# Power_Supply.net
KiCad netlist of a schematic drawn in Altium Designer
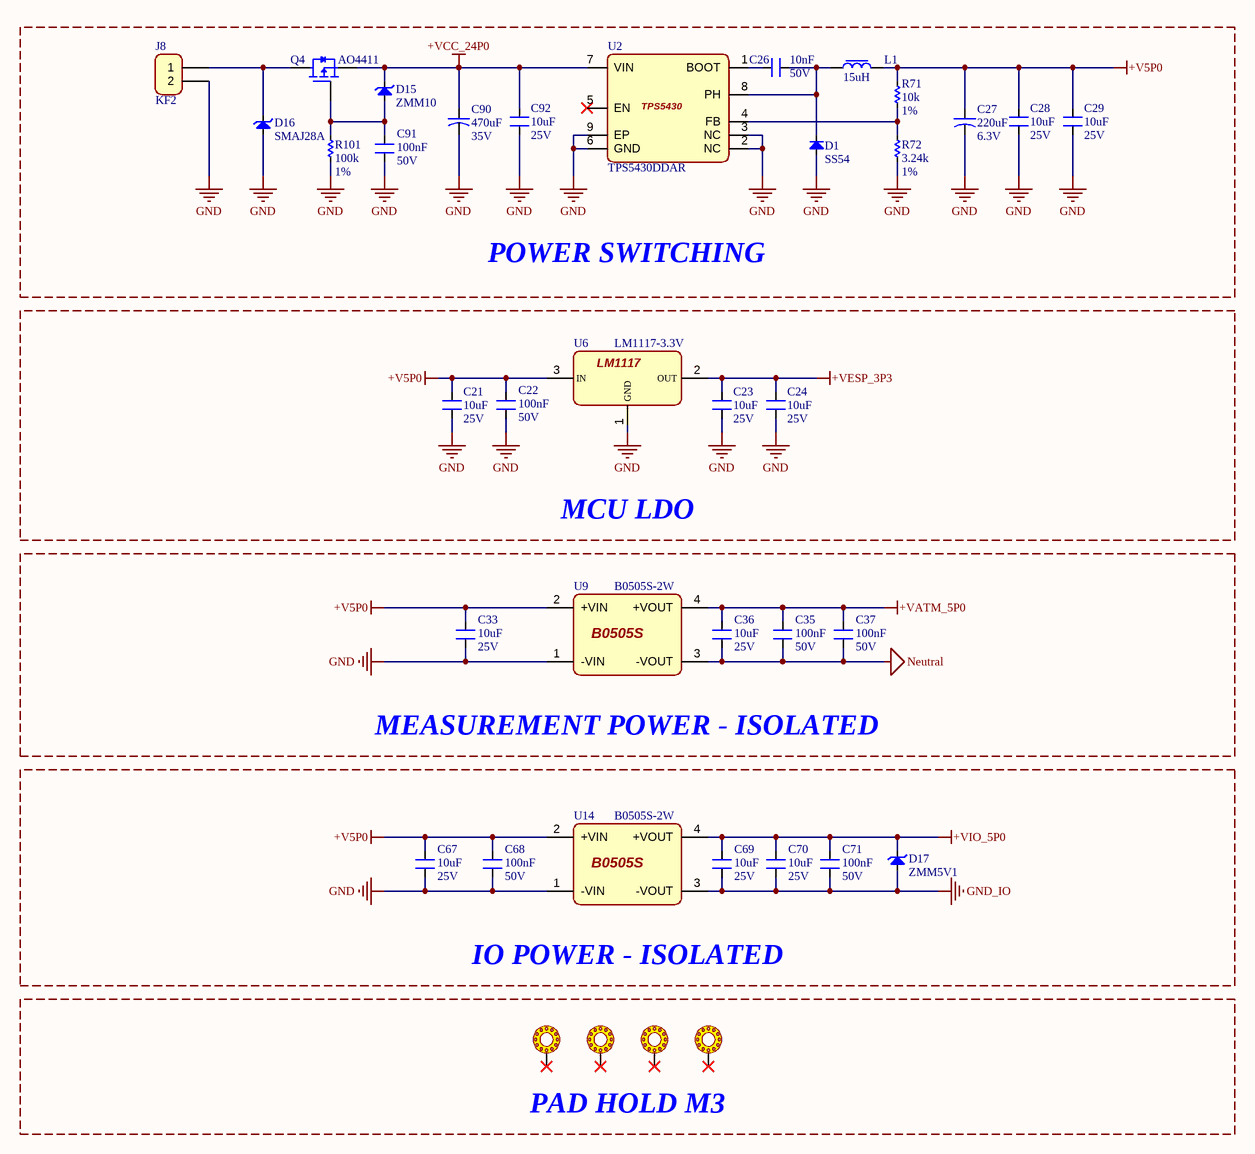
[diagram p0: Power Supply.SchDoc]

(export (version "E")
  (design (tool "Eeschema 10.0.6"))
  (components
    (comp (ref "C21")
      (value "10uF")
      (footprint "Library_HUNG:CAP_SMD_1206")
      (fields (field (name "RATING") "25V"))
      (libsource (lib "Library_HUNG") (part "CN"))
    )
    (comp (ref "C22")
      (value "100nF")
      (footprint "Library_HUNG:CAP_SMD_1206")
      (fields (field (name "RATING") "50V"))
      (libsource (lib "Library_HUNG") (part "CN"))
    )
    (comp (ref "C23")
      (value "10uF")
      (footprint "Library_HUNG:CAP_SMD_1206")
      (fields (field (name "RATING") "25V"))
      (libsource (lib "Library_HUNG") (part "CN"))
    )
    (comp (ref "C24")
      (value "10uF")
      (footprint "Library_HUNG:CAP_SMD_1206")
      (fields (field (name "RATING") "25V"))
      (libsource (lib "Library_HUNG") (part "CN"))
    )
    (comp (ref "C26")
      (value "10nF")
      (footprint "Library_HUNG:CAP_SMD_0603")
      (fields (field (name "RATING") "50V"))
      (libsource (lib "Library_HUNG") (part "CN"))
    )
    (comp (ref "C27")
      (value "220uF")
      (footprint "TANT 2312")
      (fields (field (name "RATING") "6.3V"))
      (libsource (lib "Library_HUNG") (part "CN-TANTALUM"))
    )
    (comp (ref "C28")
      (value "10uF")
      (footprint "Library_HUNG:CAP_SMD_1206")
      (fields (field (name "RATING") "25V"))
      (libsource (lib "Library_HUNG") (part "CN"))
    )
    (comp (ref "C29")
      (value "10uF")
      (footprint "Library_HUNG:CAP_SMD_1206")
      (fields (field (name "RATING") "25V"))
      (libsource (lib "Library_HUNG") (part "CN"))
    )
    (comp (ref "C33")
      (value "10uF")
      (footprint "Library_HUNG:CAP_SMD_1206")
      (fields (field (name "RATING") "25V"))
      (libsource (lib "Library_HUNG") (part "CN"))
    )
    (comp (ref "C35")
      (value "100nF")
      (footprint "Library_HUNG:CAP_SMD_1206")
      (fields (field (name "RATING") "50V"))
      (libsource (lib "Library_HUNG") (part "CN"))
    )
    (comp (ref "C36")
      (value "10uF")
      (footprint "Library_HUNG:CAP_SMD_1206")
      (fields (field (name "RATING") "25V"))
      (libsource (lib "Library_HUNG") (part "CN"))
    )
    (comp (ref "C37")
      (value "100nF")
      (footprint "Library_HUNG:CAP_SMD_1206")
      (fields (field (name "RATING") "50V"))
      (libsource (lib "Library_HUNG") (part "CN"))
    )
    (comp (ref "C67")
      (value "10uF")
      (footprint "Library_HUNG:CAP_SMD_0805")
      (fields (field (name "RATING") "25V"))
      (libsource (lib "Library_HUNG") (part "CN"))
    )
    (comp (ref "C68")
      (value "100nF")
      (footprint "Library_HUNG:CAP_SMD_0805")
      (fields (field (name "RATING") "50V"))
      (libsource (lib "Library_HUNG") (part "CN"))
    )
    (comp (ref "C69")
      (value "10uF")
      (footprint "Library_HUNG:CAP_SMD_1206")
      (fields (field (name "RATING") "25V"))
      (libsource (lib "Library_HUNG") (part "CN"))
    )
    (comp (ref "C70")
      (value "10uF")
      (footprint "Library_HUNG:CAP_SMD_1206")
      (fields (field (name "RATING") "25V"))
      (libsource (lib "Library_HUNG") (part "CN"))
    )
    (comp (ref "C71")
      (value "100nF")
      (footprint "Library_HUNG:CAP_SMD_1206")
      (fields (field (name "RATING") "50V"))
      (libsource (lib "Library_HUNG") (part "CN"))
    )
    (comp (ref "C90")
      (value "470uF")
      (footprint "Library_HUNG:CAP_ALU_10x10.2")
      (description "Polarized Capacitor (Axial)")
      (fields (field (name "RATING") "35V"))
      (libsource (lib "Library_HUNG") (part "CN-ALU-SMD"))
    )
    (comp (ref "C91")
      (value "100nF")
      (footprint "Library_HUNG:CAP_SMD_0603")
      (fields (field (name "RATING") "50V"))
      (libsource (lib "Library_HUNG") (part "CN"))
    )
    (comp (ref "C92")
      (value "10uF")
      (footprint "Library_HUNG:CAP_SMD_1206")
      (fields (field (name "RATING") "25V"))
      (libsource (lib "Library_HUNG") (part "CN"))
    )
    (comp (ref "D1")
      (value "SS54")
      (footprint "DIO-SMD-A")
      (description "Default Diode")
      (libsource (lib "Library_HUNG") (part "Diode SMD"))
    )
    (comp (ref "D15")
      (value "ZMM10")
      (footprint "SOD-80")
      (description "Zenner")
      (libsource (lib "Library_HUNG") (part "DIODE Zener"))
    )
    (comp (ref "D16")
      (value "SMAJ28A")
      (footprint "DIO-SMD-A")
      (libsource (lib "Library_HUNG") (part "TVS DIODE"))
    )
    (comp (ref "D17")
      (value "ZMM5V1")
      (footprint "SOD-80")
      (description "Zenner")
      (libsource (lib "Library_HUNG") (part "DIODE Zener"))
    )
    (comp (ref "H1")
      (value "HOLD")
      (footprint "Library_HUNG:M3-VIA")
      (libsource (lib "Library_HUNG") (part "PAD_HOLD"))
    )
    (comp (ref "H2")
      (value "HOLD")
      (footprint "Library_HUNG:M3-VIA")
      (libsource (lib "Library_HUNG") (part "PAD_HOLD"))
    )
    (comp (ref "H3")
      (value "HOLD")
      (footprint "Library_HUNG:M3-VIA")
      (libsource (lib "Library_HUNG") (part "PAD_HOLD"))
    )
    (comp (ref "H4")
      (value "HOLD")
      (footprint "Library_HUNG:M3-VIA")
      (libsource (lib "Library_HUNG") (part "PAD_HOLD"))
    )
    (comp (ref "J8") (value "KF2") (footprint "KF2-5.08X") (libsource (lib "Library_HUNG") (part "KF2")))
    (comp (ref "L1")
      (value "15uH")
      (footprint "Library_HUNG:SRP7030")
      (libsource (lib "Library_HUNG") (part "INDUCTOR"))
    )
    (comp (ref "Q4")
      (value "AO4411")
      (footprint "FET-SOIC-8")
      (libsource (lib "Library_HUNG") (part "FET-P"))
    )
    (comp (ref "R71")
      (value "10k")
      (footprint "Library_HUNG:RES_SMD_0603")
      (description "Resistor")
      (fields (field (name "TOLERANCE") "1%"))
      (libsource (lib "Library_HUNG") (part "Res-SMD"))
    )
    (comp (ref "R72")
      (value "3.24k")
      (footprint "Library_HUNG:RES_SMD_0603")
      (description "Resistor")
      (fields (field (name "TOLERANCE") "1%"))
      (libsource (lib "Library_HUNG") (part "Res-SMD"))
    )
    (comp (ref "R101")
      (value "100k")
      (footprint "Library_HUNG:RES_SMD_0603")
      (description "Resistor")
      (fields (field (name "TOLERANCE") "1%"))
      (libsource (lib "Library_HUNG") (part "Res-SMD"))
    )
    (comp (ref "U2")
      (value "TPS5430DDAR")
      (footprint "SOIC-8-EP")
      (libsource (lib "Library_HUNG") (part "TPS5430"))
    )
    (comp (ref "U6")
      (value "LM1117-3.3V")
      (footprint "SOT223-4")
      (description "800mA Low-Dropout Linear Regulator")
      (libsource (lib "Library_HUNG") (part "LM1117"))
    )
    (comp (ref "U9")
      (value "B0505S-2W")
      (footprint "SIP,19.6x7mm")
      (libsource (lib "Library_HUNG") (part "B0505S"))
    )
    (comp (ref "U14")
      (value "B0505S-2W")
      (footprint "SIP,19.6x7mm")
      (libsource (lib "Library_HUNG") (part "B0505S"))
    )
  )
  (nets
    (net (code "1") (name "+V5P0") (class "Default")
      (node (ref "C21") (pin "1") (pinfunction "1_1") (pintype "passive"))
      (node (ref "C22") (pin "2") (pinfunction "2_2") (pintype "passive"))
      (node (ref "C27") (pin "1") (pinfunction "1_1") (pintype "passive"))
      (node (ref "C28") (pin "1") (pinfunction "1_1") (pintype "passive"))
      (node (ref "C29") (pin "1") (pinfunction "1_1") (pintype "passive"))
      (node (ref "C33") (pin "2") (pinfunction "2_2") (pintype "passive"))
      (node (ref "C67") (pin "2") (pinfunction "2_2") (pintype "passive"))
      (node (ref "C68") (pin "2") (pinfunction "2_2") (pintype "passive"))
      (node (ref "L1") (pin "2") (pintype "power_in"))
      (node (ref "R71") (pin "2") (pinfunction "2_2") (pintype "passive"))
      (node (ref "U14") (pin "2") (pinfunction "+VIN_2") (pintype "power_in"))
      (node (ref "U6") (pin "3") (pinfunction "IN_3") (pintype "passive"))
      (node (ref "U9") (pin "2") (pinfunction "+VIN_2") (pintype "power_in"))
    )
    (net (code "2") (name "+VATM_5P0") (class "Default")
      (node (ref "C35") (pin "2") (pinfunction "2_2") (pintype "passive"))
      (node (ref "C36") (pin "2") (pinfunction "2_2") (pintype "passive"))
      (node (ref "C37") (pin "2") (pinfunction "2_2") (pintype "passive"))
      (node (ref "U9") (pin "4") (pinfunction "+VOUT_4") (pintype "power_in"))
    )
    (net (code "3") (name "+VCC_24P0") (class "Default")
      (node (ref "C90") (pin "1") (pinfunction "1_1") (pintype "passive"))
      (node (ref "C92") (pin "1") (pinfunction "1_1") (pintype "passive"))
      (node (ref "D15") (pin "2") (pinfunction "K_2") (pintype "passive"))
      (node (ref "Q4") (pin "2") (pintype "power_in"))
      (node (ref "U2") (pin "7") (pinfunction "VIN_7") (pintype "passive"))
    )
    (net (code "4") (name "+VESP_3P3") (class "Default")
      (node (ref "C23") (pin "1") (pinfunction "1_1") (pintype "passive"))
      (node (ref "C24") (pin "1") (pinfunction "1_1") (pintype "passive"))
      (node (ref "U6") (pin "2") (pinfunction "OUT_2") (pintype "passive"))
    )
    (net (code "5") (name "+VIO_5P0") (class "Default")
      (node (ref "C69") (pin "2") (pinfunction "2_2") (pintype "passive"))
      (node (ref "C70") (pin "2") (pinfunction "2_2") (pintype "passive"))
      (node (ref "C71") (pin "2") (pinfunction "2_2") (pintype "passive"))
      (node (ref "D17") (pin "2") (pinfunction "K_2") (pintype "passive"))
      (node (ref "U14") (pin "4") (pinfunction "+VOUT_4") (pintype "power_in"))
    )
    (net (code "6") (name "GND") (class "Default")
      (node (ref "C21") (pin "2") (pinfunction "2_2") (pintype "passive"))
      (node (ref "C22") (pin "1") (pinfunction "1_1") (pintype "passive"))
      (node (ref "C23") (pin "2") (pinfunction "2_2") (pintype "passive"))
      (node (ref "C24") (pin "2") (pinfunction "2_2") (pintype "passive"))
      (node (ref "C27") (pin "2") (pinfunction "2_2") (pintype "passive"))
      (node (ref "C28") (pin "2") (pinfunction "2_2") (pintype "passive"))
      (node (ref "C29") (pin "2") (pinfunction "2_2") (pintype "passive"))
      (node (ref "C33") (pin "1") (pinfunction "1_1") (pintype "passive"))
      (node (ref "C67") (pin "1") (pinfunction "1_1") (pintype "passive"))
      (node (ref "C68") (pin "1") (pinfunction "1_1") (pintype "passive"))
      (node (ref "C90") (pin "2") (pinfunction "2_2") (pintype "passive"))
      (node (ref "C91") (pin "1") (pinfunction "1_1") (pintype "passive"))
      (node (ref "C92") (pin "2") (pinfunction "2_2") (pintype "passive"))
      (node (ref "D1") (pin "1") (pinfunction "A_1") (pintype "passive"))
      (node (ref "D16") (pin "1") (pinfunction "A_1") (pintype "passive"))
      (node (ref "J8") (pin "2") (pinfunction "2_2") (pintype "passive"))
      (node (ref "R101") (pin "1") (pinfunction "1_1") (pintype "passive"))
      (node (ref "R72") (pin "1") (pinfunction "1_1") (pintype "passive"))
      (node (ref "U14") (pin "1") (pinfunction "-VIN_1") (pintype "power_in"))
      (node (ref "U2") (pin "2") (pinfunction "NC_2") (pintype "passive"))
      (node (ref "U2") (pin "3") (pinfunction "NC_3") (pintype "passive"))
      (node (ref "U2") (pin "6") (pinfunction "GND_6") (pintype "passive"))
      (node (ref "U2") (pin "9") (pinfunction "EP_9") (pintype "passive"))
      (node (ref "U6") (pin "1") (pinfunction "GND_1") (pintype "passive"))
      (node (ref "U9") (pin "1") (pinfunction "-VIN_1") (pintype "power_in"))
    )
    (net (code "7") (name "GND_IO") (class "Default")
      (node (ref "C69") (pin "1") (pinfunction "1_1") (pintype "passive"))
      (node (ref "C70") (pin "1") (pinfunction "1_1") (pintype "passive"))
      (node (ref "C71") (pin "1") (pinfunction "1_1") (pintype "passive"))
      (node (ref "D17") (pin "1") (pinfunction "A_1") (pintype "passive"))
      (node (ref "U14") (pin "3") (pinfunction "-VOUT_3") (pintype "power_in"))
    )
    (net (code "8") (name "Net-(D1-K)") (class "Default")
      (node (ref "C26") (pin "1") (pinfunction "1_1") (pintype "passive"))
      (node (ref "D1") (pin "2") (pinfunction "K_2") (pintype "passive"))
      (node (ref "L1") (pin "1") (pintype "power_in"))
      (node (ref "U2") (pin "8") (pinfunction "PH_8") (pintype "passive"))
    )
    (net (code "9") (name "Net-(D15-A)") (class "Default")
      (node (ref "C91") (pin "2") (pinfunction "2_2") (pintype "passive"))
      (node (ref "D15") (pin "1") (pinfunction "A_1") (pintype "passive"))
      (node (ref "Q4") (pin "1") (pintype "passive"))
      (node (ref "R101") (pin "2") (pinfunction "2_2") (pintype "passive"))
    )
    (net (code "10") (name "Net-(D16-K)") (class "Default")
      (node (ref "D16") (pin "2") (pinfunction "K_2") (pintype "passive"))
      (node (ref "J8") (pin "1") (pinfunction "1_1") (pintype "passive"))
      (node (ref "Q4") (pin "3") (pintype "power_in"))
    )
    (net (code "11") (name "Net-(U2-BOOT)") (class "Default")
      (node (ref "C26") (pin "2") (pinfunction "2_2") (pintype "passive"))
      (node (ref "U2") (pin "1") (pinfunction "BOOT_1") (pintype "passive"))
    )
    (net (code "12") (name "Net-(U2-FB)") (class "Default")
      (node (ref "R71") (pin "1") (pinfunction "1_1") (pintype "passive"))
      (node (ref "R72") (pin "2") (pinfunction "2_2") (pintype "passive"))
      (node (ref "U2") (pin "4") (pinfunction "FB_4") (pintype "passive"))
    )
    (net (code "13") (name "Neutral") (class "Default")
      (node (ref "C35") (pin "1") (pinfunction "1_1") (pintype "passive"))
      (node (ref "C36") (pin "1") (pinfunction "1_1") (pintype "passive"))
      (node (ref "C37") (pin "1") (pinfunction "1_1") (pintype "passive"))
      (node (ref "U9") (pin "3") (pinfunction "-VOUT_3") (pintype "power_in"))
    )
    (net (code "14") (name "unconnected-(H1-Pad1)") (class "Default")
      (node (ref "H1") (pin "1") (pintype "power_in+no_connect"))
    )
    (net (code "15") (name "unconnected-(H2-Pad1)") (class "Default")
      (node (ref "H2") (pin "1") (pintype "power_in+no_connect"))
    )
    (net (code "16") (name "unconnected-(H3-Pad1)") (class "Default")
      (node (ref "H3") (pin "1") (pintype "power_in+no_connect"))
    )
    (net (code "17") (name "unconnected-(H4-Pad1)") (class "Default")
      (node (ref "H4") (pin "1") (pintype "power_in+no_connect"))
    )
    (net (code "18") (name "unconnected-(U2-EN-Pad5)") (class "Default")
      (node (ref "U2") (pin "5") (pinfunction "EN_5") (pintype "passive+no_connect"))
    )
  )
)
